# R401D.net
KiCad netlist of a schematic drawn in EAGLE
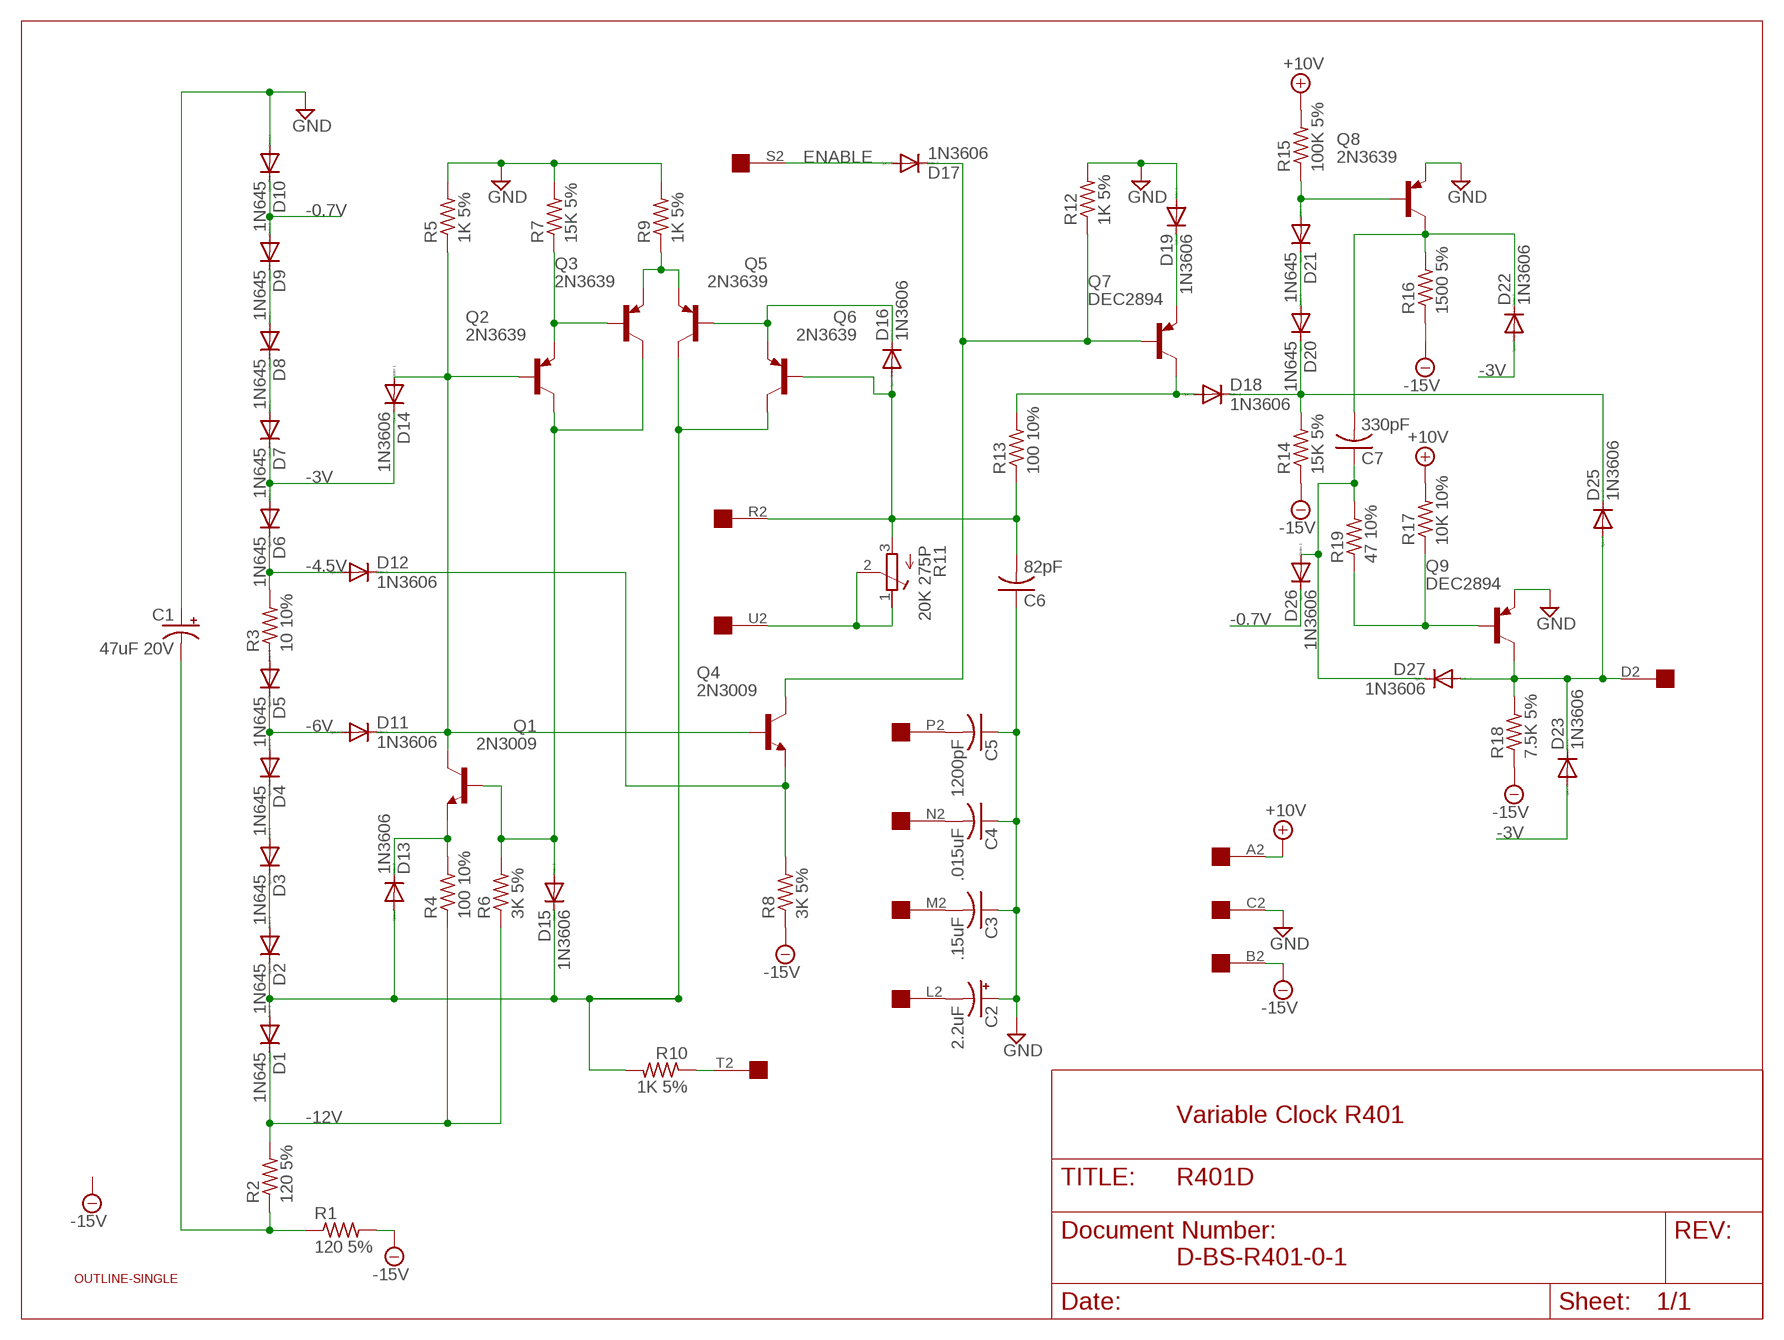
[diagram p0: schematic, sheet 1]

(export (version "E")
  (design (tool "Eeschema 10.0.6"))
  (components
    (comp (ref "C1")
      (value "47uF 20V")
      (footprint "eagle-import:E22-6")
      (libsource (lib "eagle-import") (part "CPOL-USE22-6AXIAL"))
    )
    (comp (ref "C2")
      (value "2.2uF")
      (footprint "eagle-import:E12-4")
      (libsource (lib "eagle-import") (part "CPOL-USE12-4AXIAL"))
    )
    (comp (ref "C3")
      (value ".15uF")
      (footprint "eagle-import:C275-093X316")
      (libsource (lib "eagle-import") (part "C-US275-093X316"))
    )
    (comp (ref "C4")
      (value ".015uF")
      (footprint "eagle-import:C150-054X183")
      (libsource (lib "eagle-import") (part "C-US150-054X183"))
    )
    (comp (ref "C5")
      (value "1200pF")
      (footprint "eagle-import:C102-043X133")
      (libsource (lib "eagle-import") (part "C-US102-043X133"))
    )
    (comp (ref "C6")
      (value "82pF")
      (footprint "eagle-import:C075-032X103")
      (libsource (lib "eagle-import") (part "C-US075-032X103"))
    )
    (comp (ref "C7")
      (value "330pF")
      (footprint "eagle-import:C075-032X103")
      (libsource (lib "eagle-import") (part "C-US075-032X103"))
    )
    (comp (ref "D1")
      (value "1N645")
      (footprint "eagle-import:DO35-10")
      (libsource (lib "eagle-import") (part "1N4148DO35-10"))
    )
    (comp (ref "D2")
      (value "1N645")
      (footprint "eagle-import:DO35-10")
      (libsource (lib "eagle-import") (part "1N4148DO35-10"))
    )
    (comp (ref "D3")
      (value "1N645")
      (footprint "eagle-import:DO35-10")
      (libsource (lib "eagle-import") (part "1N4148DO35-10"))
    )
    (comp (ref "D4")
      (value "1N645")
      (footprint "eagle-import:DO35-10")
      (libsource (lib "eagle-import") (part "1N4148DO35-10"))
    )
    (comp (ref "D5")
      (value "1N645")
      (footprint "eagle-import:DO35-10")
      (libsource (lib "eagle-import") (part "1N4148DO35-10"))
    )
    (comp (ref "D6")
      (value "1N645")
      (footprint "eagle-import:DO35-10")
      (libsource (lib "eagle-import") (part "1N4148DO35-10"))
    )
    (comp (ref "D7")
      (value "1N645")
      (footprint "eagle-import:DO35-10")
      (libsource (lib "eagle-import") (part "1N4148DO35-10"))
    )
    (comp (ref "D8")
      (value "1N645")
      (footprint "eagle-import:DO35-10")
      (libsource (lib "eagle-import") (part "1N4148DO35-10"))
    )
    (comp (ref "D9")
      (value "1N645")
      (footprint "eagle-import:DO35-10")
      (libsource (lib "eagle-import") (part "1N4148DO35-10"))
    )
    (comp (ref "D10")
      (value "1N645")
      (footprint "eagle-import:DO35-10")
      (libsource (lib "eagle-import") (part "1N4148DO35-10"))
    )
    (comp (ref "D11")
      (value "1N3606")
      (footprint "eagle-import:DO35-10")
      (libsource (lib "eagle-import") (part "1N4148DO35-10"))
    )
    (comp (ref "D12")
      (value "1N3606")
      (footprint "eagle-import:DO35-10")
      (libsource (lib "eagle-import") (part "1N4148DO35-10"))
    )
    (comp (ref "D13")
      (value "1N3606")
      (footprint "eagle-import:DO35-10")
      (libsource (lib "eagle-import") (part "1N4148DO35-10"))
    )
    (comp (ref "D14")
      (value "1N3606")
      (footprint "eagle-import:DO35-10")
      (libsource (lib "eagle-import") (part "1N4148DO35-10"))
    )
    (comp (ref "D15")
      (value "1N3606")
      (footprint "eagle-import:DO35-10")
      (libsource (lib "eagle-import") (part "1N4148DO35-10"))
    )
    (comp (ref "D16")
      (value "1N3606")
      (footprint "eagle-import:DO35-10")
      (libsource (lib "eagle-import") (part "1N4148DO35-10"))
    )
    (comp (ref "D17")
      (value "1N3606")
      (footprint "eagle-import:DO35-10")
      (libsource (lib "eagle-import") (part "1N4148DO35-10"))
    )
    (comp (ref "D18")
      (value "1N3606")
      (footprint "eagle-import:DO35-10")
      (libsource (lib "eagle-import") (part "1N4148DO35-10"))
    )
    (comp (ref "D19")
      (value "1N3606")
      (footprint "eagle-import:DO35-10")
      (libsource (lib "eagle-import") (part "1N4148DO35-10"))
    )
    (comp (ref "D20")
      (value "1N645")
      (footprint "eagle-import:DO35-10")
      (libsource (lib "eagle-import") (part "1N4148DO35-10"))
    )
    (comp (ref "D21")
      (value "1N645")
      (footprint "eagle-import:DO35-10")
      (libsource (lib "eagle-import") (part "1N4148DO35-10"))
    )
    (comp (ref "D22")
      (value "1N3606")
      (footprint "eagle-import:DO35-10")
      (libsource (lib "eagle-import") (part "1N4148DO35-10"))
    )
    (comp (ref "D23")
      (value "1N3606")
      (footprint "eagle-import:DO35-10")
      (libsource (lib "eagle-import") (part "1N4148DO35-10"))
    )
    (comp (ref "D25")
      (value "1N3606")
      (footprint "eagle-import:DO35-10")
      (libsource (lib "eagle-import") (part "1N4148DO35-10"))
    )
    (comp (ref "D26")
      (value "1N3606")
      (footprint "eagle-import:DO35-10")
      (libsource (lib "eagle-import") (part "1N4148DO35-10"))
    )
    (comp (ref "D27")
      (value "1N3606")
      (footprint "eagle-import:DO35-10")
      (libsource (lib "eagle-import") (part "1N4148DO35-10"))
    )
    (comp (ref "Q1")
      (value "2N3009")
      (footprint "eagle-import:TO5")
      (libsource (lib "eagle-import") (part "2N2102"))
    )
    (comp (ref "Q2")
      (value "2N3639")
      (footprint "eagle-import:TO39")
      (libsource (lib "eagle-import") (part "2N2904"))
    )
    (comp (ref "Q3")
      (value "2N3639")
      (footprint "eagle-import:TO39")
      (libsource (lib "eagle-import") (part "2N2904"))
    )
    (comp (ref "Q4")
      (value "2N3009")
      (footprint "eagle-import:TO5")
      (libsource (lib "eagle-import") (part "2N2102"))
    )
    (comp (ref "Q5")
      (value "2N3639")
      (footprint "eagle-import:TO39")
      (libsource (lib "eagle-import") (part "2N2904"))
    )
    (comp (ref "Q6")
      (value "2N3639")
      (footprint "eagle-import:TO39")
      (libsource (lib "eagle-import") (part "2N2904"))
    )
    (comp (ref "Q7")
      (value "DEC2894")
      (footprint "eagle-import:TO39")
      (libsource (lib "eagle-import") (part "2N2904"))
    )
    (comp (ref "Q8")
      (value "2N3639")
      (footprint "eagle-import:TO39")
      (libsource (lib "eagle-import") (part "2N2904"))
    )
    (comp (ref "Q9")
      (value "DEC2894")
      (footprint "eagle-import:TO39")
      (libsource (lib "eagle-import") (part "2N2904"))
    )
    (comp (ref "R1")
      (value "120 5%")
      (footprint "eagle-import:0207_10")
      (libsource (lib "eagle-import") (part "R-US_0207/10"))
    )
    (comp (ref "R2")
      (value "120 5%")
      (footprint "eagle-import:0207_10")
      (libsource (lib "eagle-import") (part "R-US_0207/10"))
    )
    (comp (ref "R3")
      (value "10 10%")
      (footprint "eagle-import:0207_10")
      (libsource (lib "eagle-import") (part "R-US_0207/10"))
    )
    (comp (ref "R4")
      (value "100 10%")
      (footprint "eagle-import:0207_10")
      (libsource (lib "eagle-import") (part "R-US_0207/10"))
    )
    (comp (ref "R5")
      (value "1K 5%")
      (footprint "eagle-import:0207_10")
      (libsource (lib "eagle-import") (part "R-US_0207/10"))
    )
    (comp (ref "R6")
      (value "3K 5%")
      (footprint "eagle-import:0207_10")
      (libsource (lib "eagle-import") (part "R-US_0207/10"))
    )
    (comp (ref "R7")
      (value "15K 5%")
      (footprint "eagle-import:0207_10")
      (libsource (lib "eagle-import") (part "R-US_0207/10"))
    )
    (comp (ref "R8")
      (value "3K 5%")
      (footprint "eagle-import:0207_10")
      (libsource (lib "eagle-import") (part "R-US_0207/10"))
    )
    (comp (ref "R9")
      (value "1K 5%")
      (footprint "eagle-import:0207_10")
      (libsource (lib "eagle-import") (part "R-US_0207/10"))
    )
    (comp (ref "R10")
      (value "1K 5%")
      (footprint "eagle-import:0207_10")
      (libsource (lib "eagle-import") (part "R-US_0207/10"))
    )
    (comp (ref "R11")
      (value "20K 275P")
      (footprint "eagle-import:3006Y")
      (libsource (lib "eagle-import") (part "275P"))
    )
    (comp (ref "R12")
      (value "1K 5%")
      (footprint "eagle-import:0207_10")
      (libsource (lib "eagle-import") (part "R-US_0207/10"))
    )
    (comp (ref "R13")
      (value "100 10%")
      (footprint "eagle-import:0207_10")
      (libsource (lib "eagle-import") (part "R-US_0207/10"))
    )
    (comp (ref "R14")
      (value "15K 5%")
      (footprint "eagle-import:0207_10")
      (libsource (lib "eagle-import") (part "R-US_0207/10"))
    )
    (comp (ref "R15")
      (value "100K 5%")
      (footprint "eagle-import:0207_10")
      (libsource (lib "eagle-import") (part "R-US_0207/10"))
    )
    (comp (ref "R16")
      (value "1500 5%")
      (footprint "eagle-import:0207_10")
      (libsource (lib "eagle-import") (part "R-US_0207/10"))
    )
    (comp (ref "R17")
      (value "10K 10%")
      (footprint "eagle-import:0207_10")
      (libsource (lib "eagle-import") (part "R-US_0207/10"))
    )
    (comp (ref "R18")
      (value "7.5K 5%")
      (footprint "eagle-import:0207_10")
      (libsource (lib "eagle-import") (part "R-US_0207/10"))
    )
    (comp (ref "R19")
      (value "47 10%")
      (footprint "eagle-import:0207_10")
      (libsource (lib "eagle-import") (part "R-US_0207/10"))
    )
    (comp (ref "U$1")
      (value "OUTLINE-SINGLE")
      (footprint "eagle-import:SINGLE")
      (libsource (lib "eagle-import") (part "OUTLINE-SINGLE"))
    )
    (comp (ref "U$2")
      (value "EDGE-1")
      (footprint "eagle-import:EDGE-CON1")
      (libsource (lib "eagle-import") (part "EDGE-1"))
    )
  )
  (nets
    (net (code "1") (name "+10V") (class "Default")
      (node (ref "R15") (pin "2") (pinfunction "2_2") (pintype "passive"))
      (node (ref "R17") (pin "2") (pinfunction "2_2") (pintype "passive"))
      (node (ref "U$2") (pin "A2") (pinfunction "1_A2") (pintype "bidirectional"))
    )
    (net (code "2") (name "-15V") (class "Default")
      (node (ref "R1") (pin "2") (pinfunction "2_2") (pintype "passive"))
      (node (ref "R14") (pin "1") (pinfunction "1_1") (pintype "passive"))
      (node (ref "R16") (pin "1") (pinfunction "1_1") (pintype "passive"))
      (node (ref "R18") (pin "1") (pinfunction "1_1") (pintype "passive"))
      (node (ref "R8") (pin "1") (pinfunction "1_1") (pintype "passive"))
      (node (ref "U$2") (pin "B2") (pinfunction "1_B2") (pintype "bidirectional"))
    )
    (net (code "3") (name "/-0.7V") (class "Default")
      (node (ref "D10") (pin "C") (pinfunction "C_C") (pintype "passive"))
      (node (ref "D26") (pin "C") (pinfunction "C_C") (pintype "passive"))
      (node (ref "D9") (pin "A") (pinfunction "A_A") (pintype "passive"))
    )
    (net (code "4") (name "/-3V") (class "Default")
      (node (ref "D14") (pin "C") (pinfunction "C_C") (pintype "passive"))
      (node (ref "D22") (pin "A") (pinfunction "A_A") (pintype "passive"))
      (node (ref "D23") (pin "A") (pinfunction "A_A") (pintype "passive"))
      (node (ref "D6") (pin "A") (pinfunction "A_A") (pintype "passive"))
      (node (ref "D7") (pin "C") (pinfunction "C_C") (pintype "passive"))
    )
    (net (code "5") (name "/-4.5V") (class "Default")
      (node (ref "D12") (pin "A") (pinfunction "A_A") (pintype "passive"))
      (node (ref "D6") (pin "C") (pinfunction "C_C") (pintype "passive"))
      (node (ref "R3") (pin "2") (pinfunction "2_2") (pintype "passive"))
    )
    (net (code "6") (name "/-6V") (class "Default")
      (node (ref "D11") (pin "A") (pinfunction "A_A") (pintype "passive"))
      (node (ref "D4") (pin "A") (pinfunction "A_A") (pintype "passive"))
      (node (ref "D5") (pin "C") (pinfunction "C_C") (pintype "passive"))
    )
    (net (code "7") (name "/-12V") (class "Default")
      (node (ref "D1") (pin "C") (pinfunction "C_C") (pintype "passive"))
      (node (ref "R2") (pin "2") (pinfunction "2_2") (pintype "passive"))
      (node (ref "R4") (pin "1") (pinfunction "1_1") (pintype "passive"))
      (node (ref "R6") (pin "1") (pinfunction "1_1") (pintype "passive"))
    )
    (net (code "8") (name "/ENABLE") (class "Default")
      (node (ref "D17") (pin "A") (pinfunction "A_A") (pintype "passive"))
      (node (ref "U$2") (pin "S2") (pinfunction "1_S2") (pintype "bidirectional"))
    )
    (net (code "9") (name "GND") (class "Default")
      (node (ref "C1") (pin "+") (pinfunction "+_+") (pintype "passive"))
      (node (ref "C2") (pin "+") (pinfunction "+_+") (pintype "passive"))
      (node (ref "C3") (pin "1") (pinfunction "1_1") (pintype "passive"))
      (node (ref "C4") (pin "1") (pinfunction "1_1") (pintype "passive"))
      (node (ref "C5") (pin "1") (pinfunction "1_1") (pintype "passive"))
      (node (ref "C6") (pin "1") (pinfunction "1_1") (pintype "passive"))
      (node (ref "D10") (pin "A") (pinfunction "A_A") (pintype "passive"))
      (node (ref "D19") (pin "A") (pinfunction "A_A") (pintype "passive"))
      (node (ref "Q8") (pin "1") (pinfunction "E_1") (pintype "passive"))
      (node (ref "Q9") (pin "1") (pinfunction "E_1") (pintype "passive"))
      (node (ref "R12") (pin "2") (pinfunction "2_2") (pintype "passive"))
      (node (ref "R5") (pin "2") (pinfunction "2_2") (pintype "passive"))
      (node (ref "R7") (pin "2") (pinfunction "2_2") (pintype "passive"))
      (node (ref "R9") (pin "2") (pinfunction "2_2") (pintype "passive"))
      (node (ref "U$2") (pin "C2") (pinfunction "1_C2") (pintype "bidirectional"))
    )
    (net (code "10") (name "Net-(C1-Pad-)") (class "Default")
      (node (ref "C1") (pin "-") (pinfunction "-_-") (pintype "passive"))
      (node (ref "R1") (pin "1") (pinfunction "1_1") (pintype "passive"))
      (node (ref "R2") (pin "1") (pinfunction "1_1") (pintype "passive"))
    )
    (net (code "11") (name "Net-(C7-Pad1)") (class "Default")
      (node (ref "C7") (pin "1") (pinfunction "1_1") (pintype "passive"))
      (node (ref "D26") (pin "A") (pinfunction "A_A") (pintype "passive"))
      (node (ref "D27") (pin "C") (pinfunction "C_C") (pintype "passive"))
      (node (ref "R19") (pin "2") (pinfunction "2_2") (pintype "passive"))
    )
    (net (code "12") (name "Net-(D2-PadA)") (class "Default")
      (node (ref "D2") (pin "A") (pinfunction "A_A") (pintype "passive"))
      (node (ref "D3") (pin "C") (pinfunction "C_C") (pintype "passive"))
    )
    (net (code "13") (name "Net-(D3-PadA)") (class "Default")
      (node (ref "D3") (pin "A") (pinfunction "A_A") (pintype "passive"))
      (node (ref "D4") (pin "C") (pinfunction "C_C") (pintype "passive"))
    )
    (net (code "14") (name "Net-(D5-PadA)") (class "Default")
      (node (ref "D5") (pin "A") (pinfunction "A_A") (pintype "passive"))
      (node (ref "R3") (pin "1") (pinfunction "1_1") (pintype "passive"))
    )
    (net (code "15") (name "Net-(D7-PadA)") (class "Default")
      (node (ref "D7") (pin "A") (pinfunction "A_A") (pintype "passive"))
      (node (ref "D8") (pin "C") (pinfunction "C_C") (pintype "passive"))
    )
    (net (code "16") (name "Net-(D8-PadA)") (class "Default")
      (node (ref "D8") (pin "A") (pinfunction "A_A") (pintype "passive"))
      (node (ref "D9") (pin "C") (pinfunction "C_C") (pintype "passive"))
    )
    (net (code "17") (name "Net-(D18-PadC)") (class "Default")
      (node (ref "D18") (pin "C") (pinfunction "C_C") (pintype "passive"))
      (node (ref "D20") (pin "C") (pinfunction "C_C") (pintype "passive"))
      (node (ref "D25") (pin "C") (pinfunction "C_C") (pintype "passive"))
      (node (ref "R14") (pin "2") (pinfunction "2_2") (pintype "passive"))
    )
    (net (code "18") (name "Net-(D20-PadA)") (class "Default")
      (node (ref "D20") (pin "A") (pinfunction "A_A") (pintype "passive"))
      (node (ref "D21") (pin "C") (pinfunction "C_C") (pintype "passive"))
    )
    (net (code "19") (name "Net-(Q1-B)") (class "Default")
      (node (ref "D15") (pin "A") (pinfunction "A_A") (pintype "passive"))
      (node (ref "Q1") (pin "2") (pinfunction "B_2") (pintype "passive"))
      (node (ref "Q2") (pin "3") (pinfunction "C_3") (pintype "passive"))
      (node (ref "Q3") (pin "3") (pinfunction "C_3") (pintype "passive"))
      (node (ref "R6") (pin "2") (pinfunction "2_2") (pintype "passive"))
    )
    (net (code "20") (name "Net-(Q1-C)") (class "Default")
      (node (ref "D11") (pin "C") (pinfunction "C_C") (pintype "passive"))
      (node (ref "D14") (pin "A") (pinfunction "A_A") (pintype "passive"))
      (node (ref "Q1") (pin "3") (pinfunction "C_3") (pintype "passive"))
      (node (ref "Q2") (pin "2") (pinfunction "B_2") (pintype "passive"))
      (node (ref "Q4") (pin "2") (pinfunction "B_2") (pintype "passive"))
      (node (ref "R5") (pin "1") (pinfunction "1_1") (pintype "passive"))
    )
    (net (code "21") (name "Net-(Q1-E)") (class "Default")
      (node (ref "D13") (pin "C") (pinfunction "C_C") (pintype "passive"))
      (node (ref "Q1") (pin "1") (pinfunction "E_1") (pintype "passive"))
      (node (ref "R4") (pin "2") (pinfunction "2_2") (pintype "passive"))
    )
    (net (code "22") (name "Net-(Q2-E)") (class "Default")
      (node (ref "Q2") (pin "1") (pinfunction "E_1") (pintype "passive"))
      (node (ref "Q3") (pin "2") (pinfunction "B_2") (pintype "passive"))
      (node (ref "R7") (pin "1") (pinfunction "1_1") (pintype "passive"))
    )
    (net (code "23") (name "Net-(Q3-E)") (class "Default")
      (node (ref "Q3") (pin "1") (pinfunction "E_1") (pintype "passive"))
      (node (ref "Q5") (pin "1") (pinfunction "E_1") (pintype "passive"))
      (node (ref "R9") (pin "1") (pinfunction "1_1") (pintype "passive"))
    )
    (net (code "24") (name "Net-(Q4-C)") (class "Default")
      (node (ref "D17") (pin "C") (pinfunction "C_C") (pintype "passive"))
      (node (ref "Q4") (pin "3") (pinfunction "C_3") (pintype "passive"))
      (node (ref "Q7") (pin "2") (pinfunction "B_2") (pintype "passive"))
      (node (ref "R12") (pin "1") (pinfunction "1_1") (pintype "passive"))
    )
    (net (code "25") (name "Net-(Q4-E)") (class "Default")
      (node (ref "D12") (pin "C") (pinfunction "C_C") (pintype "passive"))
      (node (ref "Q4") (pin "1") (pinfunction "E_1") (pintype "passive"))
      (node (ref "R8") (pin "2") (pinfunction "2_2") (pintype "passive"))
    )
    (net (code "26") (name "Net-(Q5-B)") (class "Default")
      (node (ref "D16") (pin "C") (pinfunction "C_C") (pintype "passive"))
      (node (ref "Q5") (pin "2") (pinfunction "B_2") (pintype "passive"))
      (node (ref "Q6") (pin "1") (pinfunction "E_1") (pintype "passive"))
    )
    (net (code "27") (name "Net-(Q5-C)") (class "Default")
      (node (ref "D1") (pin "A") (pinfunction "A_A") (pintype "passive"))
      (node (ref "D13") (pin "A") (pinfunction "A_A") (pintype "passive"))
      (node (ref "D15") (pin "C") (pinfunction "C_C") (pintype "passive"))
      (node (ref "D2") (pin "C") (pinfunction "C_C") (pintype "passive"))
      (node (ref "Q5") (pin "3") (pinfunction "C_3") (pintype "passive"))
      (node (ref "Q6") (pin "3") (pinfunction "C_3") (pintype "passive"))
      (node (ref "R10") (pin "2") (pinfunction "2_2") (pintype "passive"))
    )
    (net (code "28") (name "Net-(Q6-B)") (class "Default")
      (node (ref "C6") (pin "2") (pinfunction "2_2") (pintype "passive"))
      (node (ref "D16") (pin "A") (pinfunction "A_A") (pintype "passive"))
      (node (ref "Q6") (pin "2") (pinfunction "B_2") (pintype "passive"))
      (node (ref "R11") (pin "3") (pinfunction "E_3") (pintype "passive"))
      (node (ref "R13") (pin "1") (pinfunction "1_1") (pintype "passive"))
      (node (ref "U$2") (pin "R2") (pinfunction "1_R2") (pintype "bidirectional"))
    )
    (net (code "29") (name "Net-(Q7-C)") (class "Default")
      (node (ref "D18") (pin "A") (pinfunction "A_A") (pintype "passive"))
      (node (ref "Q7") (pin "3") (pinfunction "C_3") (pintype "passive"))
      (node (ref "R13") (pin "2") (pinfunction "2_2") (pintype "passive"))
    )
    (net (code "30") (name "Net-(Q7-E)") (class "Default")
      (node (ref "D19") (pin "C") (pinfunction "C_C") (pintype "passive"))
      (node (ref "Q7") (pin "1") (pinfunction "E_1") (pintype "passive"))
    )
    (net (code "31") (name "Net-(Q8-B)") (class "Default")
      (node (ref "D21") (pin "A") (pinfunction "A_A") (pintype "passive"))
      (node (ref "Q8") (pin "2") (pinfunction "B_2") (pintype "passive"))
      (node (ref "R15") (pin "1") (pinfunction "1_1") (pintype "passive"))
    )
    (net (code "32") (name "Net-(Q8-C)") (class "Default")
      (node (ref "C7") (pin "2") (pinfunction "2_2") (pintype "passive"))
      (node (ref "D22") (pin "C") (pinfunction "C_C") (pintype "passive"))
      (node (ref "Q8") (pin "3") (pinfunction "C_3") (pintype "passive"))
      (node (ref "R16") (pin "2") (pinfunction "2_2") (pintype "passive"))
    )
    (net (code "33") (name "Net-(Q9-B)") (class "Default")
      (node (ref "Q9") (pin "2") (pinfunction "B_2") (pintype "passive"))
      (node (ref "R17") (pin "1") (pinfunction "1_1") (pintype "passive"))
      (node (ref "R19") (pin "1") (pinfunction "1_1") (pintype "passive"))
    )
    (net (code "34") (name "Net-(Q9-C)") (class "Default")
      (node (ref "D23") (pin "C") (pinfunction "C_C") (pintype "passive"))
      (node (ref "D25") (pin "A") (pinfunction "A_A") (pintype "passive"))
      (node (ref "D27") (pin "A") (pinfunction "A_A") (pintype "passive"))
      (node (ref "Q9") (pin "3") (pinfunction "C_3") (pintype "passive"))
      (node (ref "R18") (pin "2") (pinfunction "2_2") (pintype "passive"))
      (node (ref "U$2") (pin "D2") (pinfunction "1_D2") (pintype "bidirectional"))
    )
    (net (code "35") (name "Net-(R11-A)") (class "Default")
      (node (ref "R11") (pin "1") (pinfunction "A_1") (pintype "passive"))
      (node (ref "R11") (pin "2") (pinfunction "S_2") (pintype "passive"))
      (node (ref "U$2") (pin "U2") (pinfunction "1_U2") (pintype "bidirectional"))
    )
    (net (code "36") (name "Net-(U$2J-1)") (class "Default")
      (node (ref "C2") (pin "-") (pinfunction "-_-") (pintype "passive"))
      (node (ref "U$2") (pin "L2") (pinfunction "1_L2") (pintype "bidirectional"))
    )
    (net (code "37") (name "Net-(U$2K-1)") (class "Default")
      (node (ref "C3") (pin "2") (pinfunction "2_2") (pintype "passive"))
      (node (ref "U$2") (pin "M2") (pinfunction "1_M2") (pintype "bidirectional"))
    )
    (net (code "38") (name "Net-(U$2L-1)") (class "Default")
      (node (ref "C4") (pin "2") (pinfunction "2_2") (pintype "passive"))
      (node (ref "U$2") (pin "N2") (pinfunction "1_N2") (pintype "bidirectional"))
    )
    (net (code "39") (name "Net-(U$2M-1)") (class "Default")
      (node (ref "C5") (pin "2") (pinfunction "2_2") (pintype "passive"))
      (node (ref "U$2") (pin "P2") (pinfunction "1_P2") (pintype "bidirectional"))
    )
    (net (code "40") (name "Net-(U$2P-1)") (class "Default")
      (node (ref "R10") (pin "1") (pinfunction "1_1") (pintype "passive"))
      (node (ref "U$2") (pin "T2") (pinfunction "1_T2") (pintype "bidirectional"))
    )
  )
)
